# ADC_Unity_Gain.net
KiCad netlist of a schematic drawn in Altium Designer
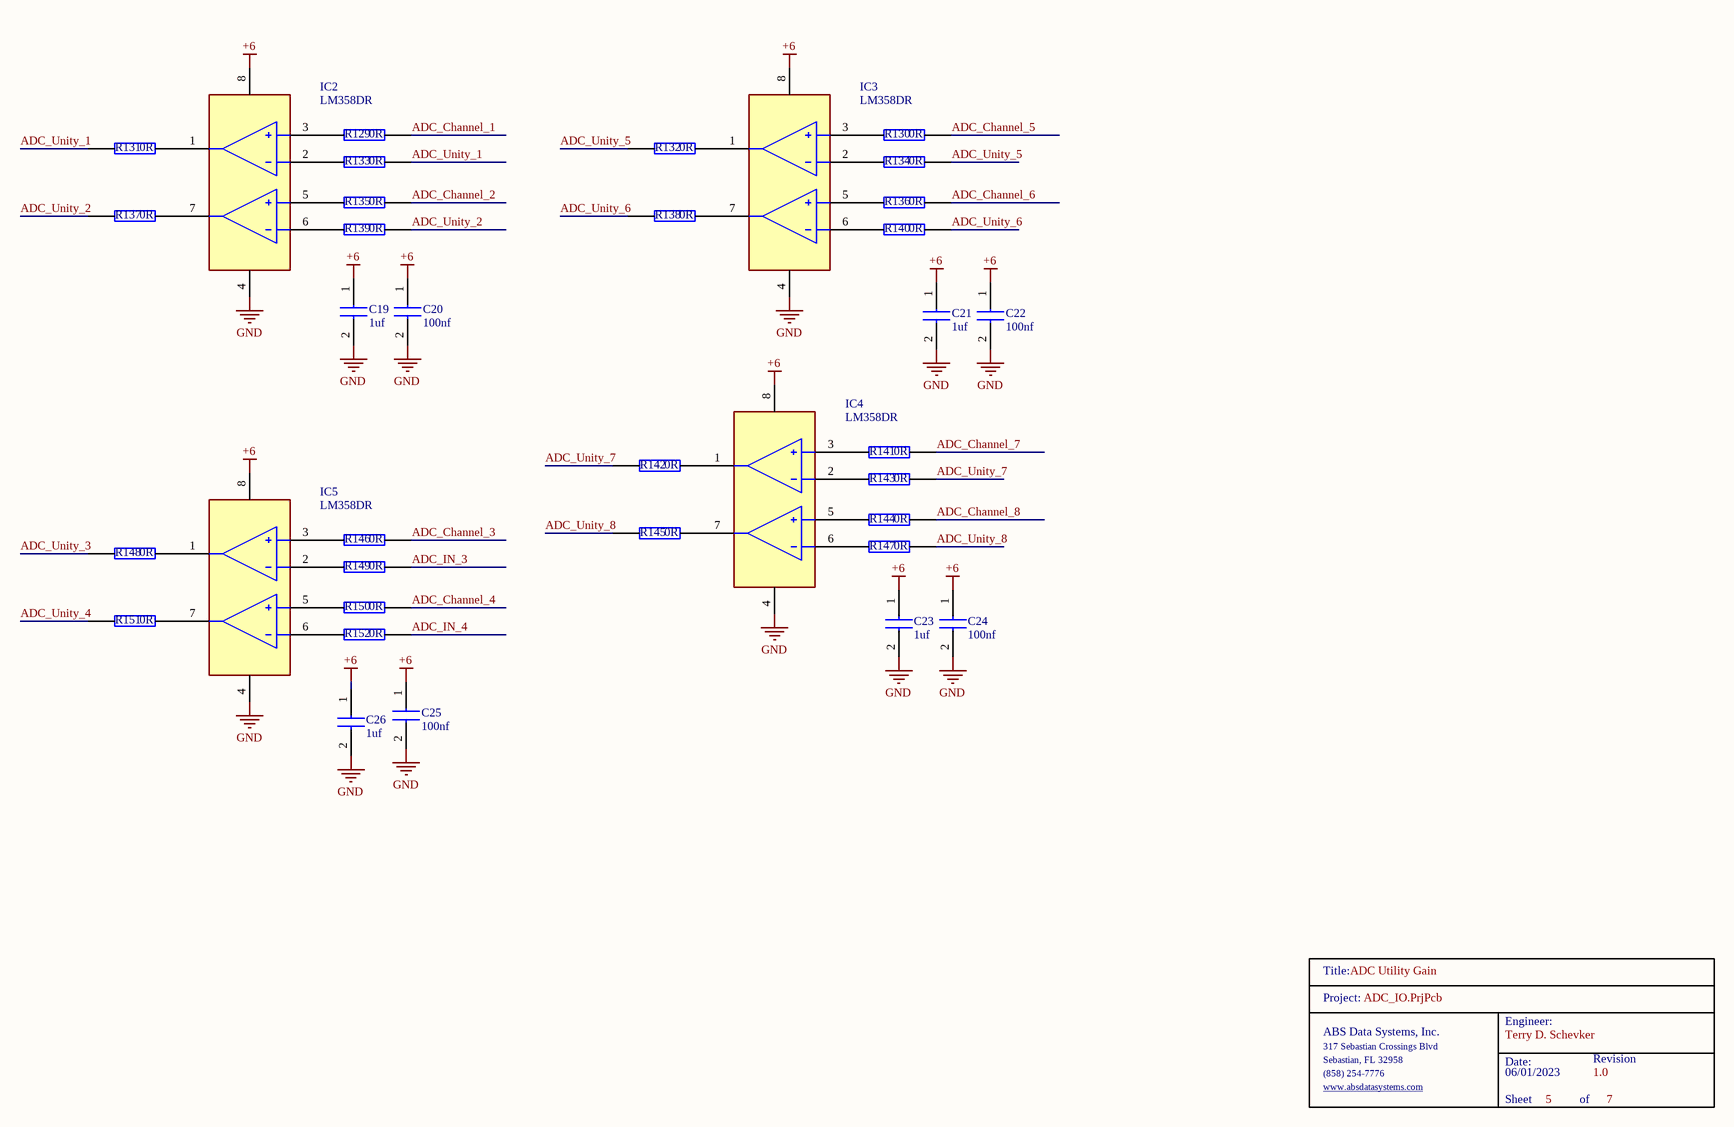
[diagram p0: ADC_Unity_Gain.SchDoc]

(export (version "E")
  (design (tool "Eeschema 10.0.6"))
  (components
    (comp (ref "C19")
      (value "1uf")
      (footprint "0603")
      (description "Samsung Electro-Mechanics 0603 1uf")
      (libsource (lib "Capacitors") (part "CL10B105KA8NNNL"))
    )
    (comp (ref "C20")
      (value "100nf")
      (footprint "0603")
      (description "Samsung Electro-Mechanics 0603 100nf")
      (libsource (lib "Capacitors") (part "CL10B104JB8NNNC"))
    )
    (comp (ref "C21")
      (value "1uf")
      (footprint "0603")
      (description "Samsung Electro-Mechanics 0603 1uf")
      (libsource (lib "Capacitors") (part "CL10B105KA8NNNL"))
    )
    (comp (ref "C22")
      (value "100nf")
      (footprint "0603")
      (description "Samsung Electro-Mechanics 0603 100nf")
      (libsource (lib "Capacitors") (part "CL10B104JB8NNNC"))
    )
    (comp (ref "C23")
      (value "1uf")
      (footprint "0603")
      (description "Samsung Electro-Mechanics 0603 1uf")
      (libsource (lib "Capacitors") (part "CL10B105KA8NNNL"))
    )
    (comp (ref "C24")
      (value "100nf")
      (footprint "0603")
      (description "Samsung Electro-Mechanics 0603 100nf")
      (libsource (lib "Capacitors") (part "CL10B104JB8NNNC"))
    )
    (comp (ref "C25")
      (value "100nf")
      (footprint "0603")
      (description "Samsung Electro-Mechanics 0603 100nf")
      (libsource (lib "Capacitors") (part "CL10B104JB8NNNC"))
    )
    (comp (ref "C26")
      (value "1uf")
      (footprint "0603")
      (description "Samsung Electro-Mechanics 0603 1uf")
      (libsource (lib "Capacitors") (part "CL10B105KA8NNNL"))
    )
    (comp (ref "IC2")
      (value "LM358DR")
      (footprint "SOIC127P600X175-8N")
      (description "Integrated Circuit")
      (fields (field (name "MOUSER PART NUMBER") "595-LM358DR"))
      (libsource (lib "SemiConductors") (part "LM358DR"))
    )
    (comp (ref "IC3")
      (value "LM358DR")
      (footprint "SOIC127P600X175-8N")
      (description "Integrated Circuit")
      (fields (field (name "MOUSER PART NUMBER") "595-LM358DR"))
      (libsource (lib "SemiConductors") (part "LM358DR"))
    )
    (comp (ref "IC4")
      (value "LM358DR")
      (footprint "SOIC127P600X175-8N")
      (description "Integrated Circuit")
      (fields (field (name "MOUSER PART NUMBER") "595-LM358DR"))
      (libsource (lib "SemiConductors") (part "LM358DR"))
    )
    (comp (ref "IC5")
      (value "LM358DR")
      (footprint "SOIC127P600X175-8N")
      (description "Integrated Circuit")
      (fields (field (name "MOUSER PART NUMBER") "595-LM358DR"))
      (libsource (lib "SemiConductors") (part "LM358DR"))
    )
    (comp (ref "R129")
      (value "0R")
      (footprint "0603")
      (description "YAGEO 0603 0 ohm")
      (fields
        (field (name "MOUSER PART NUMBER") "603-RC0603JR-070RL")
        (field (name "MANUFACTURER_PART_NUMBER") "RC0603JR-070RL")
      )
      (libsource (lib "Resistors") (part "RC0603JR-070RL"))
    )
    (comp (ref "R130")
      (value "0R")
      (footprint "0603")
      (description "YAGEO 0603 0 ohm")
      (fields
        (field (name "MOUSER PART NUMBER") "603-RC0603JR-070RL")
        (field (name "MANUFACTURER_PART_NUMBER") "RC0603JR-070RL")
      )
      (libsource (lib "Resistors") (part "RC0603JR-070RL"))
    )
    (comp (ref "R131")
      (value "0R")
      (footprint "0603")
      (description "YAGEO 0603 0 ohm")
      (fields
        (field (name "MOUSER PART NUMBER") "603-RC0603JR-070RL")
        (field (name "MANUFACTURER_PART_NUMBER") "RC0603JR-070RL")
      )
      (libsource (lib "Resistors") (part "RC0603JR-070RL"))
    )
    (comp (ref "R132")
      (value "0R")
      (footprint "0603")
      (description "YAGEO 0603 0 ohm")
      (fields
        (field (name "MOUSER PART NUMBER") "603-RC0603JR-070RL")
        (field (name "MANUFACTURER_PART_NUMBER") "RC0603JR-070RL")
      )
      (libsource (lib "Resistors") (part "RC0603JR-070RL"))
    )
    (comp (ref "R133")
      (value "0R")
      (footprint "0603")
      (description "YAGEO 0603 0 ohm")
      (fields
        (field (name "MOUSER PART NUMBER") "603-RC0603JR-070RL")
        (field (name "MANUFACTURER_PART_NUMBER") "RC0603JR-070RL")
      )
      (libsource (lib "Resistors") (part "RC0603JR-070RL"))
    )
    (comp (ref "R134")
      (value "0R")
      (footprint "0603")
      (description "YAGEO 0603 0 ohm")
      (fields
        (field (name "MOUSER PART NUMBER") "603-RC0603JR-070RL")
        (field (name "MANUFACTURER_PART_NUMBER") "RC0603JR-070RL")
      )
      (libsource (lib "Resistors") (part "RC0603JR-070RL"))
    )
    (comp (ref "R135")
      (value "0R")
      (footprint "0603")
      (description "YAGEO 0603 0 ohm")
      (fields
        (field (name "MOUSER PART NUMBER") "603-RC0603JR-070RL")
        (field (name "MANUFACTURER_PART_NUMBER") "RC0603JR-070RL")
      )
      (libsource (lib "Resistors") (part "RC0603JR-070RL"))
    )
    (comp (ref "R136")
      (value "0R")
      (footprint "0603")
      (description "YAGEO 0603 0 ohm")
      (fields
        (field (name "MOUSER PART NUMBER") "603-RC0603JR-070RL")
        (field (name "MANUFACTURER_PART_NUMBER") "RC0603JR-070RL")
      )
      (libsource (lib "Resistors") (part "RC0603JR-070RL"))
    )
    (comp (ref "R137")
      (value "0R")
      (footprint "0603")
      (description "YAGEO 0603 0 ohm")
      (fields
        (field (name "MOUSER PART NUMBER") "603-RC0603JR-070RL")
        (field (name "MANUFACTURER_PART_NUMBER") "RC0603JR-070RL")
      )
      (libsource (lib "Resistors") (part "RC0603JR-070RL"))
    )
    (comp (ref "R138")
      (value "0R")
      (footprint "0603")
      (description "YAGEO 0603 0 ohm")
      (fields
        (field (name "MOUSER PART NUMBER") "603-RC0603JR-070RL")
        (field (name "MANUFACTURER_PART_NUMBER") "RC0603JR-070RL")
      )
      (libsource (lib "Resistors") (part "RC0603JR-070RL"))
    )
    (comp (ref "R139")
      (value "0R")
      (footprint "0603")
      (description "YAGEO 0603 0 ohm")
      (fields
        (field (name "MOUSER PART NUMBER") "603-RC0603JR-070RL")
        (field (name "MANUFACTURER_PART_NUMBER") "RC0603JR-070RL")
      )
      (libsource (lib "Resistors") (part "RC0603JR-070RL"))
    )
    (comp (ref "R140")
      (value "0R")
      (footprint "0603")
      (description "YAGEO 0603 0 ohm")
      (fields
        (field (name "MOUSER PART NUMBER") "603-RC0603JR-070RL")
        (field (name "MANUFACTURER_PART_NUMBER") "RC0603JR-070RL")
      )
      (libsource (lib "Resistors") (part "RC0603JR-070RL"))
    )
    (comp (ref "R141")
      (value "0R")
      (footprint "0603")
      (description "YAGEO 0603 0 ohm")
      (fields
        (field (name "MOUSER PART NUMBER") "603-RC0603JR-070RL")
        (field (name "MANUFACTURER_PART_NUMBER") "RC0603JR-070RL")
      )
      (libsource (lib "Resistors") (part "RC0603JR-070RL"))
    )
    (comp (ref "R142")
      (value "0R")
      (footprint "0603")
      (description "YAGEO 0603 0 ohm")
      (fields
        (field (name "MOUSER PART NUMBER") "603-RC0603JR-070RL")
        (field (name "MANUFACTURER_PART_NUMBER") "RC0603JR-070RL")
      )
      (libsource (lib "Resistors") (part "RC0603JR-070RL"))
    )
    (comp (ref "R143")
      (value "0R")
      (footprint "0603")
      (description "YAGEO 0603 0 ohm")
      (fields
        (field (name "MOUSER PART NUMBER") "603-RC0603JR-070RL")
        (field (name "MANUFACTURER_PART_NUMBER") "RC0603JR-070RL")
      )
      (libsource (lib "Resistors") (part "RC0603JR-070RL"))
    )
    (comp (ref "R144")
      (value "0R")
      (footprint "0603")
      (description "YAGEO 0603 0 ohm")
      (fields
        (field (name "MOUSER PART NUMBER") "603-RC0603JR-070RL")
        (field (name "MANUFACTURER_PART_NUMBER") "RC0603JR-070RL")
      )
      (libsource (lib "Resistors") (part "RC0603JR-070RL"))
    )
    (comp (ref "R145")
      (value "0R")
      (footprint "0603")
      (description "YAGEO 0603 0 ohm")
      (fields
        (field (name "MOUSER PART NUMBER") "603-RC0603JR-070RL")
        (field (name "MANUFACTURER_PART_NUMBER") "RC0603JR-070RL")
      )
      (libsource (lib "Resistors") (part "RC0603JR-070RL"))
    )
    (comp (ref "R146")
      (value "0R")
      (footprint "0603")
      (description "YAGEO 0603 0 ohm")
      (fields
        (field (name "MOUSER PART NUMBER") "603-RC0603JR-070RL")
        (field (name "MANUFACTURER_PART_NUMBER") "RC0603JR-070RL")
      )
      (libsource (lib "Resistors") (part "RC0603JR-070RL"))
    )
    (comp (ref "R147")
      (value "0R")
      (footprint "0603")
      (description "YAGEO 0603 0 ohm")
      (fields
        (field (name "MOUSER PART NUMBER") "603-RC0603JR-070RL")
        (field (name "MANUFACTURER_PART_NUMBER") "RC0603JR-070RL")
      )
      (libsource (lib "Resistors") (part "RC0603JR-070RL"))
    )
    (comp (ref "R148")
      (value "0R")
      (footprint "0603")
      (description "YAGEO 0603 0 ohm")
      (fields
        (field (name "MOUSER PART NUMBER") "603-RC0603JR-070RL")
        (field (name "MANUFACTURER_PART_NUMBER") "RC0603JR-070RL")
      )
      (libsource (lib "Resistors") (part "RC0603JR-070RL"))
    )
    (comp (ref "R149")
      (value "0R")
      (footprint "0603")
      (description "YAGEO 0603 0 ohm")
      (fields
        (field (name "MOUSER PART NUMBER") "603-RC0603JR-070RL")
        (field (name "MANUFACTURER_PART_NUMBER") "RC0603JR-070RL")
      )
      (libsource (lib "Resistors") (part "RC0603JR-070RL"))
    )
    (comp (ref "R150")
      (value "0R")
      (footprint "0603")
      (description "YAGEO 0603 0 ohm")
      (fields
        (field (name "MOUSER PART NUMBER") "603-RC0603JR-070RL")
        (field (name "MANUFACTURER_PART_NUMBER") "RC0603JR-070RL")
      )
      (libsource (lib "Resistors") (part "RC0603JR-070RL"))
    )
    (comp (ref "R151")
      (value "0R")
      (footprint "0603")
      (description "YAGEO 0603 0 ohm")
      (fields
        (field (name "MOUSER PART NUMBER") "603-RC0603JR-070RL")
        (field (name "MANUFACTURER_PART_NUMBER") "RC0603JR-070RL")
      )
      (libsource (lib "Resistors") (part "RC0603JR-070RL"))
    )
    (comp (ref "R152")
      (value "0R")
      (footprint "0603")
      (description "YAGEO 0603 0 ohm")
      (fields
        (field (name "MOUSER PART NUMBER") "603-RC0603JR-070RL")
        (field (name "MANUFACTURER_PART_NUMBER") "RC0603JR-070RL")
      )
      (libsource (lib "Resistors") (part "RC0603JR-070RL"))
    )
    (comp (ref "TitleBlock_5") (value "TitleBlock") (libsource (lib "Misc") (part "TitleBlock")))
  )
  (nets
    (net (code "1") (name "+6") (class "Default")
      (node (ref "C19") (pin "1") (pinfunction "1_1") (pintype "passive"))
      (node (ref "C20") (pin "1") (pinfunction "1_1") (pintype "passive"))
      (node (ref "C21") (pin "1") (pinfunction "1_1") (pintype "passive"))
      (node (ref "C22") (pin "1") (pinfunction "1_1") (pintype "passive"))
      (node (ref "C23") (pin "1") (pinfunction "1_1") (pintype "passive"))
      (node (ref "C24") (pin "1") (pinfunction "1_1") (pintype "passive"))
      (node (ref "C25") (pin "1") (pinfunction "1_1") (pintype "passive"))
      (node (ref "C26") (pin "1") (pinfunction "1_1") (pintype "passive"))
      (node (ref "IC2") (pin "8") (pinfunction "V+_8") (pintype "passive"))
      (node (ref "IC3") (pin "8") (pinfunction "V+_8") (pintype "passive"))
      (node (ref "IC4") (pin "8") (pinfunction "V+_8") (pintype "passive"))
      (node (ref "IC5") (pin "8") (pinfunction "V+_8") (pintype "passive"))
    )
    (net (code "2") (name "/ADC_Channel_1") (class "Default")
      (node (ref "R129") (pin "2") (pinfunction "2_2") (pintype "passive"))
    )
    (net (code "3") (name "/ADC_Channel_2") (class "Default")
      (node (ref "R135") (pin "2") (pinfunction "2_2") (pintype "passive"))
    )
    (net (code "4") (name "/ADC_Channel_3") (class "Default")
      (node (ref "R146") (pin "2") (pinfunction "2_2") (pintype "passive"))
    )
    (net (code "5") (name "/ADC_Channel_4") (class "Default")
      (node (ref "R150") (pin "2") (pinfunction "2_2") (pintype "passive"))
    )
    (net (code "6") (name "/ADC_Channel_5") (class "Default")
      (node (ref "R130") (pin "2") (pinfunction "2_2") (pintype "passive"))
    )
    (net (code "7") (name "/ADC_Channel_6") (class "Default")
      (node (ref "R136") (pin "2") (pinfunction "2_2") (pintype "passive"))
    )
    (net (code "8") (name "/ADC_Channel_7") (class "Default")
      (node (ref "R141") (pin "2") (pinfunction "2_2") (pintype "passive"))
    )
    (net (code "9") (name "/ADC_Channel_8") (class "Default")
      (node (ref "R144") (pin "2") (pinfunction "2_2") (pintype "passive"))
    )
    (net (code "10") (name "/ADC_IN_3") (class "Default")
      (node (ref "R149") (pin "2") (pinfunction "2_2") (pintype "passive"))
    )
    (net (code "11") (name "/ADC_IN_4") (class "Default")
      (node (ref "R152") (pin "2") (pinfunction "2_2") (pintype "passive"))
    )
    (net (code "12") (name "/ADC_Unity_1") (class "Default")
      (node (ref "R131") (pin "1") (pinfunction "1_1") (pintype "passive"))
      (node (ref "R133") (pin "2") (pinfunction "2_2") (pintype "passive"))
    )
    (net (code "13") (name "/ADC_Unity_2") (class "Default")
      (node (ref "R137") (pin "1") (pinfunction "1_1") (pintype "passive"))
      (node (ref "R139") (pin "2") (pinfunction "2_2") (pintype "passive"))
    )
    (net (code "14") (name "/ADC_Unity_3") (class "Default")
      (node (ref "R148") (pin "1") (pinfunction "1_1") (pintype "passive"))
    )
    (net (code "15") (name "/ADC_Unity_4") (class "Default")
      (node (ref "R151") (pin "1") (pinfunction "1_1") (pintype "passive"))
    )
    (net (code "16") (name "/ADC_Unity_5") (class "Default")
      (node (ref "R132") (pin "1") (pinfunction "1_1") (pintype "passive"))
      (node (ref "R134") (pin "2") (pinfunction "2_2") (pintype "passive"))
    )
    (net (code "17") (name "/ADC_Unity_6") (class "Default")
      (node (ref "R138") (pin "1") (pinfunction "1_1") (pintype "passive"))
      (node (ref "R140") (pin "2") (pinfunction "2_2") (pintype "passive"))
    )
    (net (code "18") (name "/ADC_Unity_7") (class "Default")
      (node (ref "R142") (pin "1") (pinfunction "1_1") (pintype "passive"))
      (node (ref "R143") (pin "2") (pinfunction "2_2") (pintype "passive"))
    )
    (net (code "19") (name "/ADC_Unity_8") (class "Default")
      (node (ref "R145") (pin "1") (pinfunction "1_1") (pintype "passive"))
      (node (ref "R147") (pin "2") (pinfunction "2_2") (pintype "passive"))
    )
    (net (code "20") (name "GND") (class "Default")
      (node (ref "C19") (pin "2") (pinfunction "2_2") (pintype "passive"))
      (node (ref "C20") (pin "2") (pinfunction "2_2") (pintype "passive"))
      (node (ref "C21") (pin "2") (pinfunction "2_2") (pintype "passive"))
      (node (ref "C22") (pin "2") (pinfunction "2_2") (pintype "passive"))
      (node (ref "C23") (pin "2") (pinfunction "2_2") (pintype "passive"))
      (node (ref "C24") (pin "2") (pinfunction "2_2") (pintype "passive"))
      (node (ref "C25") (pin "2") (pinfunction "2_2") (pintype "passive"))
      (node (ref "C26") (pin "2") (pinfunction "2_2") (pintype "passive"))
      (node (ref "IC2") (pin "4") (pinfunction "V-_4") (pintype "passive"))
      (node (ref "IC3") (pin "4") (pinfunction "V-_4") (pintype "passive"))
      (node (ref "IC4") (pin "4") (pinfunction "V-_4") (pintype "passive"))
      (node (ref "IC5") (pin "4") (pinfunction "V-_4") (pintype "passive"))
    )
    (net (code "21") (name "Net-(IC2-IN1+)") (class "Default")
      (node (ref "IC2") (pin "3") (pinfunction "IN1+_3") (pintype "passive"))
      (node (ref "R129") (pin "1") (pinfunction "1_1") (pintype "passive"))
    )
    (net (code "22") (name "Net-(IC2-IN1-)") (class "Default")
      (node (ref "IC2") (pin "2") (pinfunction "IN1-_2") (pintype "passive"))
      (node (ref "R133") (pin "1") (pinfunction "1_1") (pintype "passive"))
    )
    (net (code "23") (name "Net-(IC2-IN2+)") (class "Default")
      (node (ref "IC2") (pin "5") (pinfunction "IN2+_5") (pintype "passive"))
      (node (ref "R135") (pin "1") (pinfunction "1_1") (pintype "passive"))
    )
    (net (code "24") (name "Net-(IC2-IN2-)") (class "Default")
      (node (ref "IC2") (pin "6") (pinfunction "IN2-_6") (pintype "passive"))
      (node (ref "R139") (pin "1") (pinfunction "1_1") (pintype "passive"))
    )
    (net (code "25") (name "Net-(IC2-OUT1)") (class "Default")
      (node (ref "IC2") (pin "1") (pinfunction "OUT1_1") (pintype "passive"))
      (node (ref "R131") (pin "2") (pinfunction "2_2") (pintype "passive"))
    )
    (net (code "26") (name "Net-(IC2-OUT2)") (class "Default")
      (node (ref "IC2") (pin "7") (pinfunction "OUT2_7") (pintype "passive"))
      (node (ref "R137") (pin "2") (pinfunction "2_2") (pintype "passive"))
    )
    (net (code "27") (name "Net-(IC3-IN1+)") (class "Default")
      (node (ref "IC3") (pin "3") (pinfunction "IN1+_3") (pintype "passive"))
      (node (ref "R130") (pin "1") (pinfunction "1_1") (pintype "passive"))
    )
    (net (code "28") (name "Net-(IC3-IN1-)") (class "Default")
      (node (ref "IC3") (pin "2") (pinfunction "IN1-_2") (pintype "passive"))
      (node (ref "R134") (pin "1") (pinfunction "1_1") (pintype "passive"))
    )
    (net (code "29") (name "Net-(IC3-IN2+)") (class "Default")
      (node (ref "IC3") (pin "5") (pinfunction "IN2+_5") (pintype "passive"))
      (node (ref "R136") (pin "1") (pinfunction "1_1") (pintype "passive"))
    )
    (net (code "30") (name "Net-(IC3-IN2-)") (class "Default")
      (node (ref "IC3") (pin "6") (pinfunction "IN2-_6") (pintype "passive"))
      (node (ref "R140") (pin "1") (pinfunction "1_1") (pintype "passive"))
    )
    (net (code "31") (name "Net-(IC3-OUT1)") (class "Default")
      (node (ref "IC3") (pin "1") (pinfunction "OUT1_1") (pintype "passive"))
      (node (ref "R132") (pin "2") (pinfunction "2_2") (pintype "passive"))
    )
    (net (code "32") (name "Net-(IC3-OUT2)") (class "Default")
      (node (ref "IC3") (pin "7") (pinfunction "OUT2_7") (pintype "passive"))
      (node (ref "R138") (pin "2") (pinfunction "2_2") (pintype "passive"))
    )
    (net (code "33") (name "Net-(IC4-IN1+)") (class "Default")
      (node (ref "IC4") (pin "3") (pinfunction "IN1+_3") (pintype "passive"))
      (node (ref "R141") (pin "1") (pinfunction "1_1") (pintype "passive"))
    )
    (net (code "34") (name "Net-(IC4-IN1-)") (class "Default")
      (node (ref "IC4") (pin "2") (pinfunction "IN1-_2") (pintype "passive"))
      (node (ref "R143") (pin "1") (pinfunction "1_1") (pintype "passive"))
    )
    (net (code "35") (name "Net-(IC4-IN2+)") (class "Default")
      (node (ref "IC4") (pin "5") (pinfunction "IN2+_5") (pintype "passive"))
      (node (ref "R144") (pin "1") (pinfunction "1_1") (pintype "passive"))
    )
    (net (code "36") (name "Net-(IC4-IN2-)") (class "Default")
      (node (ref "IC4") (pin "6") (pinfunction "IN2-_6") (pintype "passive"))
      (node (ref "R147") (pin "1") (pinfunction "1_1") (pintype "passive"))
    )
    (net (code "37") (name "Net-(IC4-OUT1)") (class "Default")
      (node (ref "IC4") (pin "1") (pinfunction "OUT1_1") (pintype "passive"))
      (node (ref "R142") (pin "2") (pinfunction "2_2") (pintype "passive"))
    )
    (net (code "38") (name "Net-(IC4-OUT2)") (class "Default")
      (node (ref "IC4") (pin "7") (pinfunction "OUT2_7") (pintype "passive"))
      (node (ref "R145") (pin "2") (pinfunction "2_2") (pintype "passive"))
    )
    (net (code "39") (name "Net-(IC5-IN1+)") (class "Default")
      (node (ref "IC5") (pin "3") (pinfunction "IN1+_3") (pintype "passive"))
      (node (ref "R146") (pin "1") (pinfunction "1_1") (pintype "passive"))
    )
    (net (code "40") (name "Net-(IC5-IN1-)") (class "Default")
      (node (ref "IC5") (pin "2") (pinfunction "IN1-_2") (pintype "passive"))
      (node (ref "R149") (pin "1") (pinfunction "1_1") (pintype "passive"))
    )
    (net (code "41") (name "Net-(IC5-IN2+)") (class "Default")
      (node (ref "IC5") (pin "5") (pinfunction "IN2+_5") (pintype "passive"))
      (node (ref "R150") (pin "1") (pinfunction "1_1") (pintype "passive"))
    )
    (net (code "42") (name "Net-(IC5-IN2-)") (class "Default")
      (node (ref "IC5") (pin "6") (pinfunction "IN2-_6") (pintype "passive"))
      (node (ref "R152") (pin "1") (pinfunction "1_1") (pintype "passive"))
    )
    (net (code "43") (name "Net-(IC5-OUT1)") (class "Default")
      (node (ref "IC5") (pin "1") (pinfunction "OUT1_1") (pintype "passive"))
      (node (ref "R148") (pin "2") (pinfunction "2_2") (pintype "passive"))
    )
    (net (code "44") (name "Net-(IC5-OUT2)") (class "Default")
      (node (ref "IC5") (pin "7") (pinfunction "OUT2_7") (pintype "passive"))
      (node (ref "R151") (pin "2") (pinfunction "2_2") (pintype "passive"))
    )
  )
)
